# FPGA.net
KiCad netlist of a schematic drawn in EAGLE
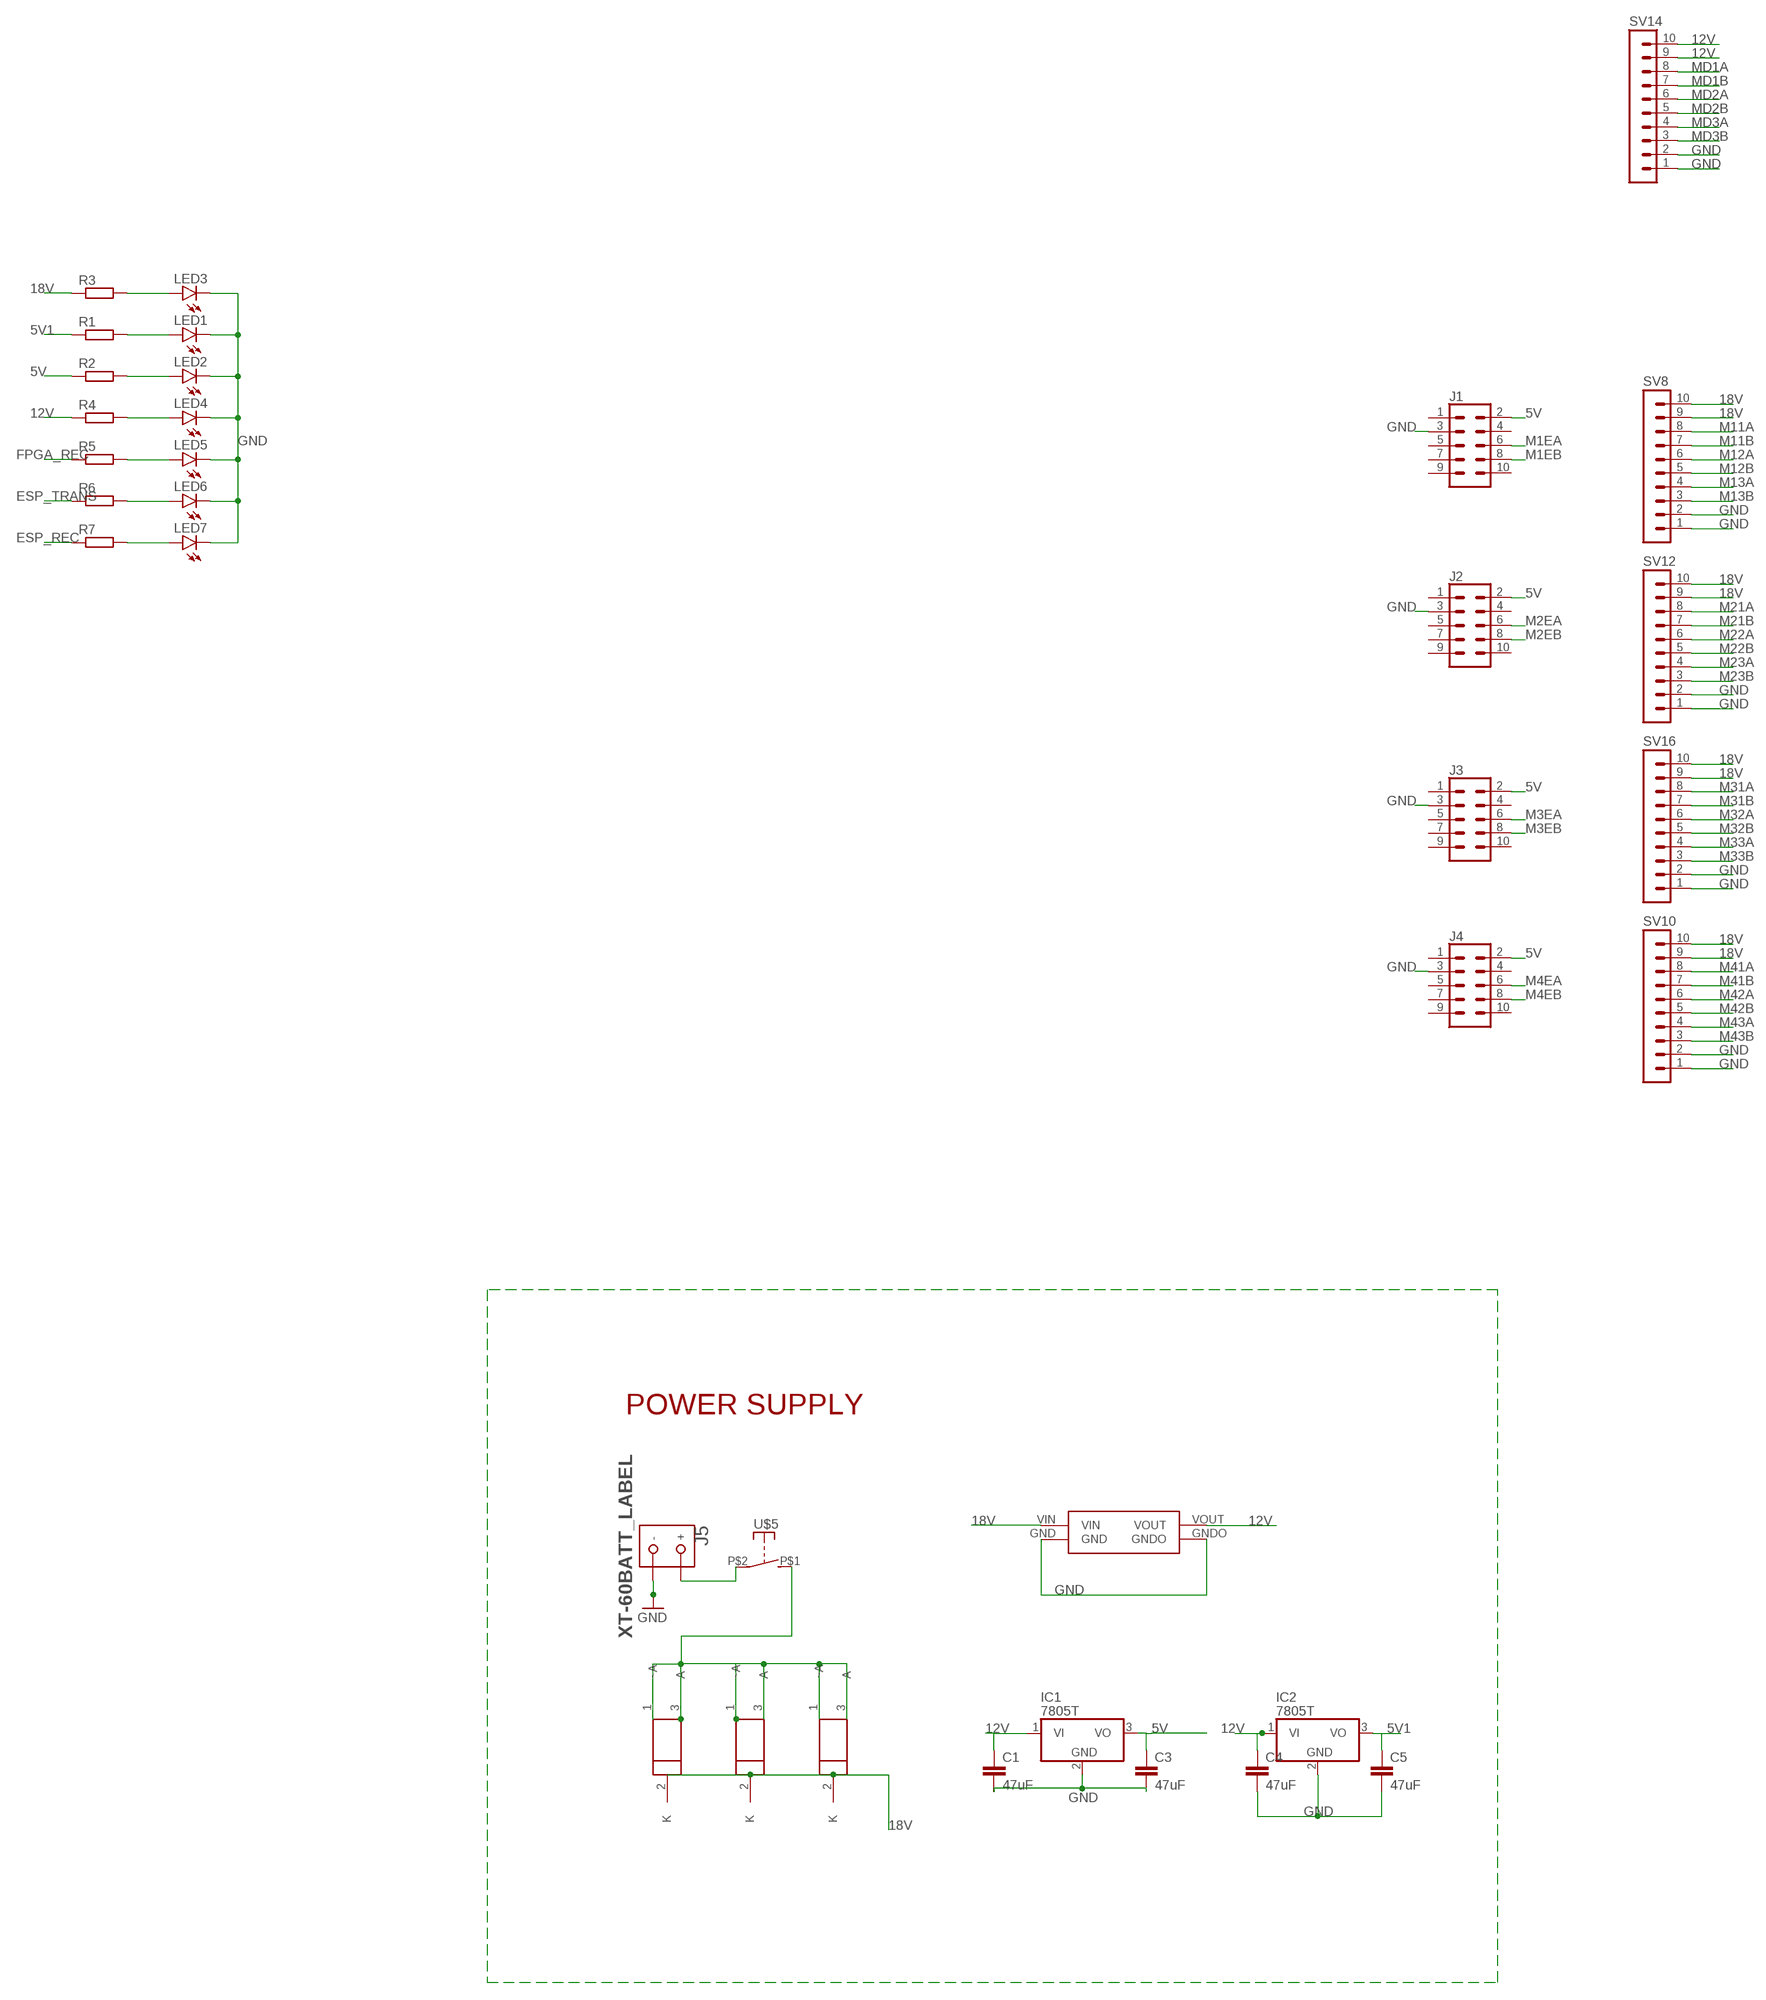
[diagram p0: schematic, sheet 1, part 1 of 2]
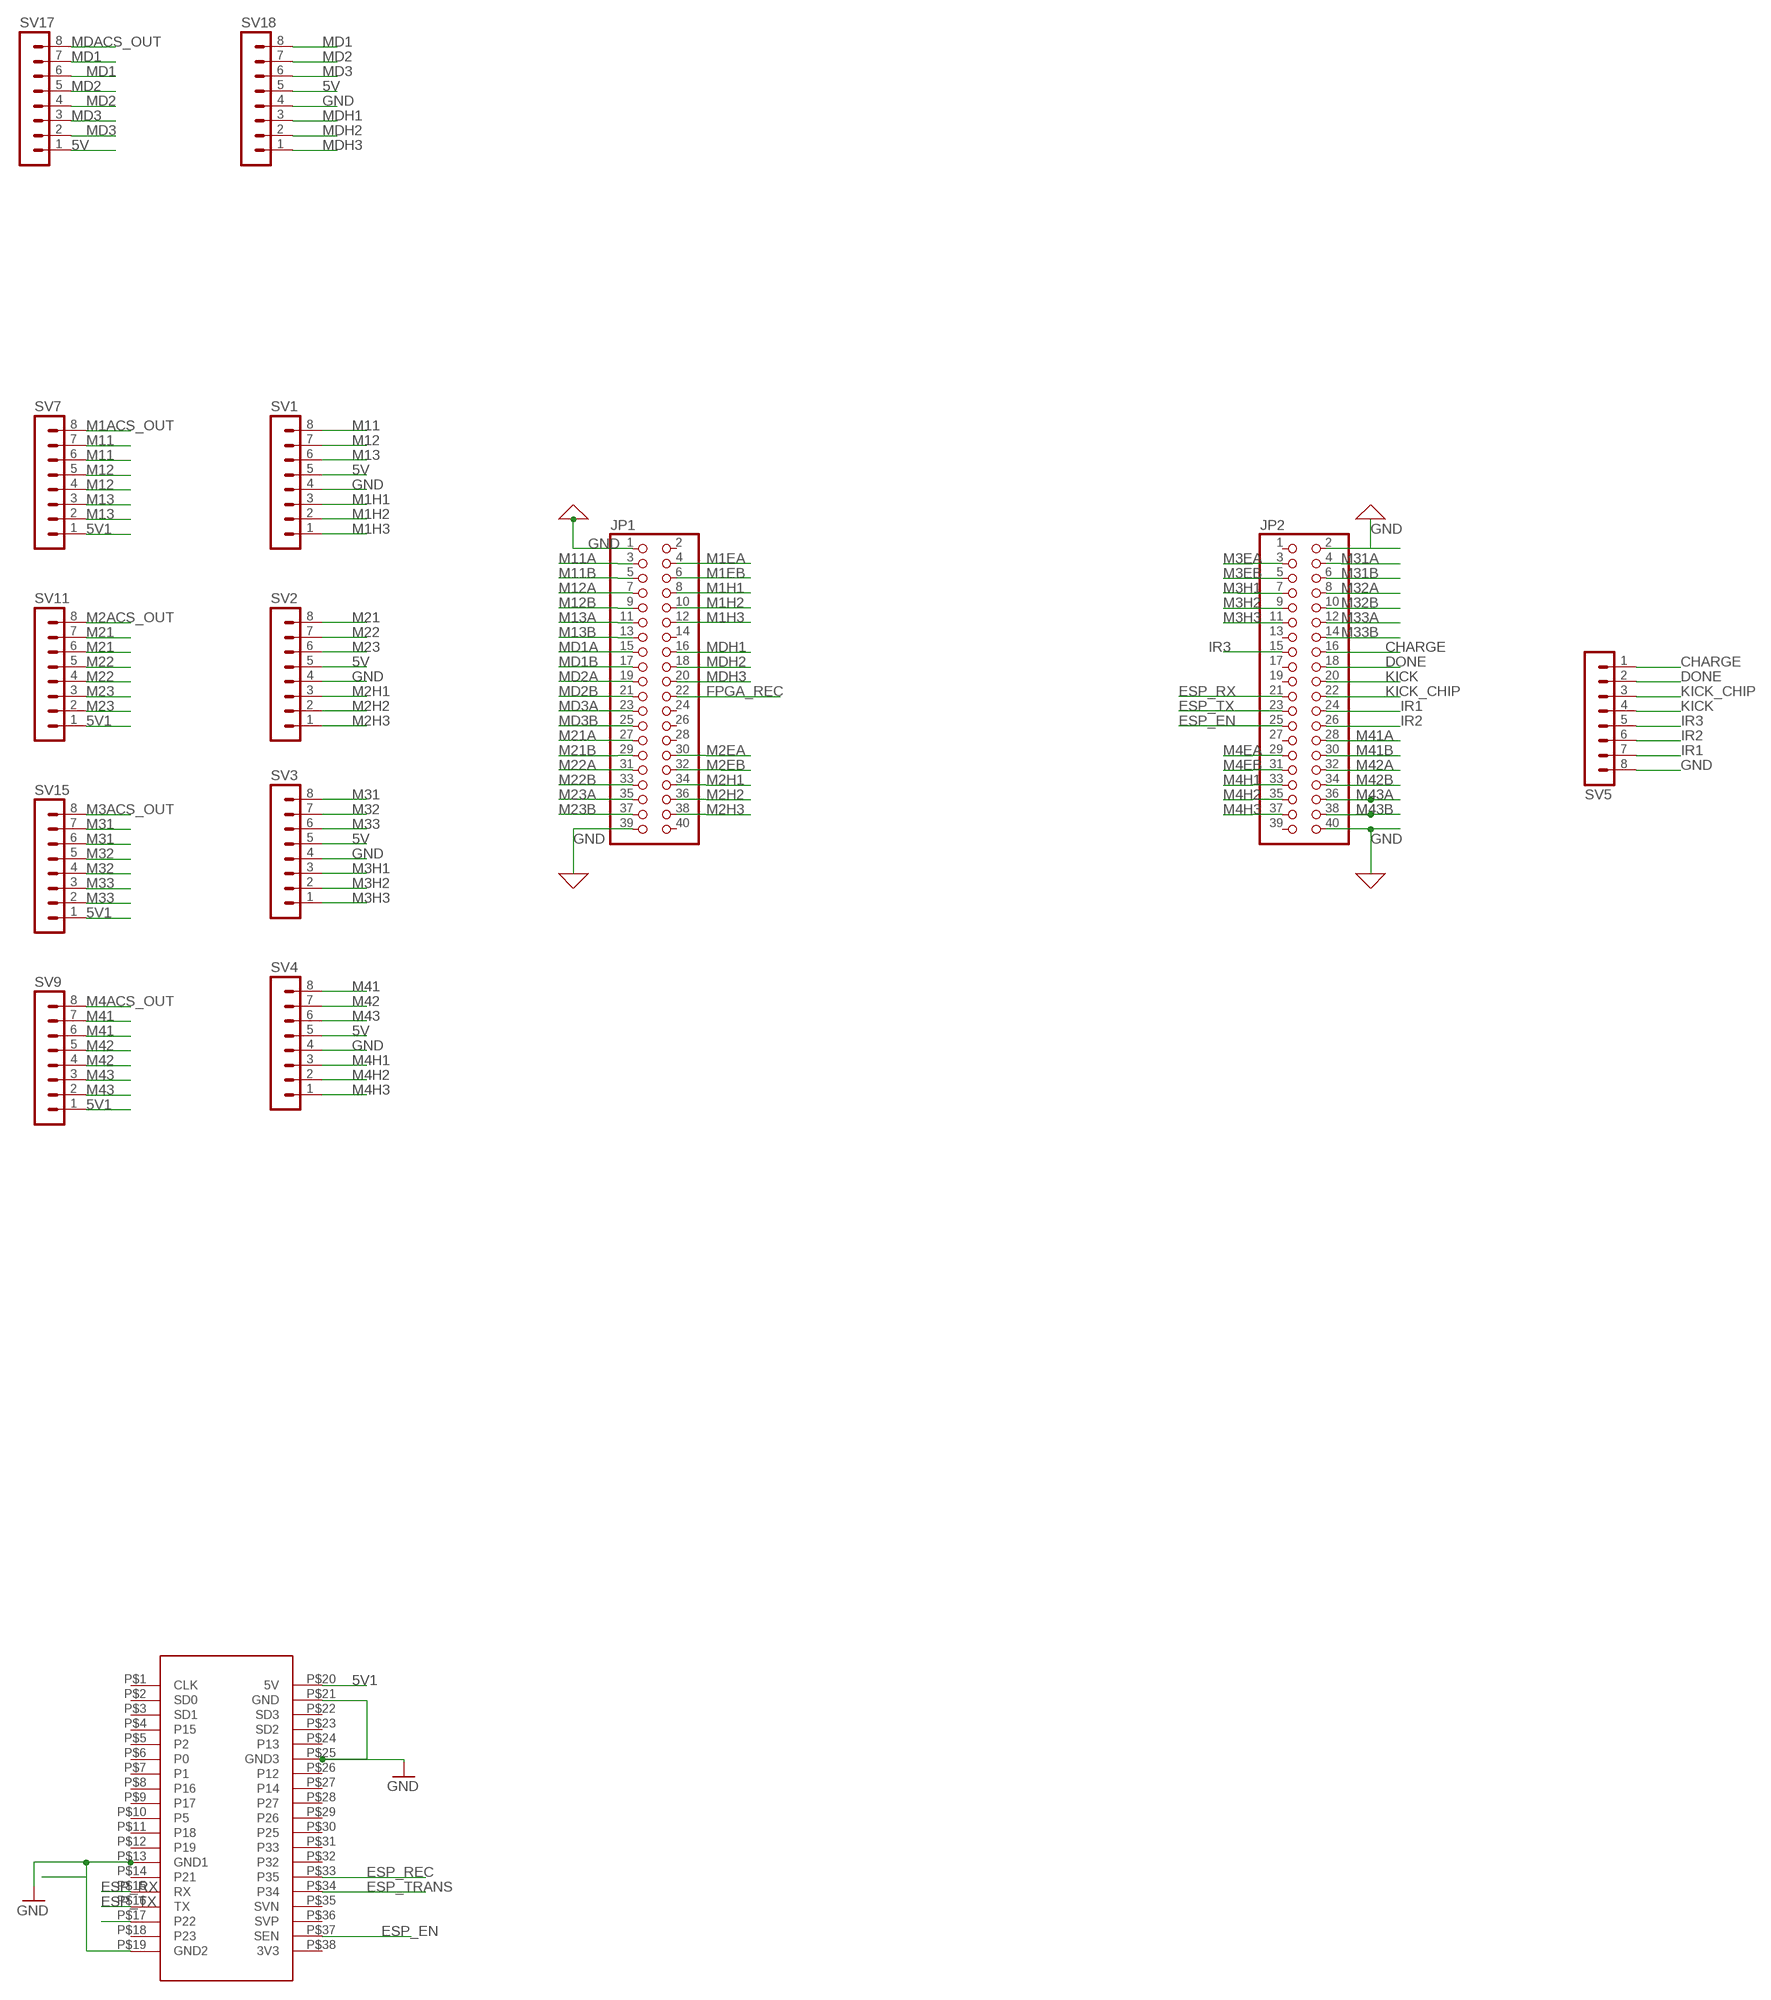
[diagram p1: schematic, sheet 1, part 2 of 2]

(export (version "E")
  (design (tool "Eeschema 10.0.6"))
  (components
    (comp (ref "C1")
      (value "47uF")
      (footprint "eagle-import:C1206")
      (libsource (lib "eagle-import") (part "C-EUC1206"))
    )
    (comp (ref "C3")
      (value "47uF")
      (footprint "eagle-import:C1206")
      (libsource (lib "eagle-import") (part "C-EUC1206"))
    )
    (comp (ref "C4")
      (value "47uF")
      (footprint "eagle-import:C1206")
      (libsource (lib "eagle-import") (part "C-EUC1206"))
    )
    (comp (ref "C5")
      (value "47uF")
      (footprint "eagle-import:C1206")
      (libsource (lib "eagle-import") (part "C-EUC1206"))
    )
    (comp (ref "IC1")
      (value "7805T")
      (footprint "eagle-import:TO220H")
      (libsource (lib "eagle-import") (part "78T05"))
    )
    (comp (ref "IC2")
      (value "7805T")
      (footprint "eagle-import:TO220H")
      (libsource (lib "eagle-import") (part "78T05"))
    )
    (comp (ref "J1")
      (value "CONN_05X2SHD_LOCK")
      (footprint "eagle-import:2X5-SHROUDED_LOCK")
      (libsource (lib "eagle-import") (part "CONN_05X2SHD_LOCK"))
    )
    (comp (ref "J2")
      (value "CONN_05X2SHD_LOCK")
      (footprint "eagle-import:2X5-SHROUDED_LOCK")
      (libsource (lib "eagle-import") (part "CONN_05X2SHD_LOCK"))
    )
    (comp (ref "J3")
      (value "CONN_05X2SHD_LOCK")
      (footprint "eagle-import:2X5-SHROUDED_LOCK")
      (libsource (lib "eagle-import") (part "CONN_05X2SHD_LOCK"))
    )
    (comp (ref "J4")
      (value "CONN_05X2SHD_LOCK")
      (footprint "eagle-import:2X5-SHROUDED_LOCK")
      (libsource (lib "eagle-import") (part "CONN_05X2SHD_LOCK"))
    )
    (comp (ref "J5")
      (value "XT-60BATT_LABEL")
      (footprint "eagle-import:XT-60")
      (libsource (lib "eagle-import") (part "XT-60BATT_LABEL"))
    )
    (comp (ref "JP1")
      (value "PINHD-2X20")
      (footprint "eagle-import:2X20")
      (libsource (lib "eagle-import") (part "PINHD-2X20"))
    )
    (comp (ref "JP2")
      (value "PINHD-2X20")
      (footprint "eagle-import:2X20")
      (libsource (lib "eagle-import") (part "PINHD-2X20"))
    )
    (comp (ref "LED1")
      (value "LEDSMT1206")
      (footprint "eagle-import:1206")
      (libsource (lib "eagle-import") (part "LEDSMT1206"))
    )
    (comp (ref "LED2")
      (value "LEDSMT1206")
      (footprint "eagle-import:1206")
      (libsource (lib "eagle-import") (part "LEDSMT1206"))
    )
    (comp (ref "LED3")
      (value "LEDSMT1206")
      (footprint "eagle-import:1206")
      (libsource (lib "eagle-import") (part "LEDSMT1206"))
    )
    (comp (ref "LED4")
      (value "LEDSMT1206")
      (footprint "eagle-import:1206")
      (libsource (lib "eagle-import") (part "LEDSMT1206"))
    )
    (comp (ref "LED5")
      (value "LEDSMT1206")
      (footprint "eagle-import:1206")
      (libsource (lib "eagle-import") (part "LEDSMT1206"))
    )
    (comp (ref "LED6")
      (value "LEDSMT1206")
      (footprint "eagle-import:1206")
      (libsource (lib "eagle-import") (part "LEDSMT1206"))
    )
    (comp (ref "LED7")
      (value "LEDSMT1206")
      (footprint "eagle-import:1206")
      (libsource (lib "eagle-import") (part "LEDSMT1206"))
    )
    (comp (ref "R1")
      (value "R-EU_R1206")
      (footprint "eagle-import:R1206")
      (libsource (lib "eagle-import") (part "R-EU_R1206"))
    )
    (comp (ref "R2")
      (value "R-EU_R1206")
      (footprint "eagle-import:R1206")
      (libsource (lib "eagle-import") (part "R-EU_R1206"))
    )
    (comp (ref "R3")
      (value "R-EU_R1206")
      (footprint "eagle-import:R1206")
      (libsource (lib "eagle-import") (part "R-EU_R1206"))
    )
    (comp (ref "R4")
      (value "R-EU_R1206")
      (footprint "eagle-import:R1206")
      (libsource (lib "eagle-import") (part "R-EU_R1206"))
    )
    (comp (ref "R5")
      (value "R-EU_R1206")
      (footprint "eagle-import:R1206")
      (libsource (lib "eagle-import") (part "R-EU_R1206"))
    )
    (comp (ref "R6")
      (value "R-EU_R1206")
      (footprint "eagle-import:R1206")
      (libsource (lib "eagle-import") (part "R-EU_R1206"))
    )
    (comp (ref "R7")
      (value "R-EU_R1206")
      (footprint "eagle-import:R1206")
      (libsource (lib "eagle-import") (part "R-EU_R1206"))
    )
    (comp (ref "SV1")
      (value "MA08-1")
      (footprint "eagle-import:MA08-1")
      (libsource (lib "eagle-import") (part "MA08-1"))
    )
    (comp (ref "SV2")
      (value "MA08-1")
      (footprint "eagle-import:MA08-1")
      (libsource (lib "eagle-import") (part "MA08-1"))
    )
    (comp (ref "SV3")
      (value "MA08-1")
      (footprint "eagle-import:MA08-1")
      (libsource (lib "eagle-import") (part "MA08-1"))
    )
    (comp (ref "SV4")
      (value "MA08-1")
      (footprint "eagle-import:MA08-1")
      (libsource (lib "eagle-import") (part "MA08-1"))
    )
    (comp (ref "SV5")
      (value "MA08-1")
      (footprint "eagle-import:MA08-1")
      (libsource (lib "eagle-import") (part "MA08-1"))
    )
    (comp (ref "SV7")
      (value "MA08-1")
      (footprint "eagle-import:MA08-1")
      (libsource (lib "eagle-import") (part "MA08-1"))
    )
    (comp (ref "SV8")
      (value "MA10-1")
      (footprint "eagle-import:MA10-1")
      (libsource (lib "eagle-import") (part "MA10-1"))
    )
    (comp (ref "SV9")
      (value "MA08-1")
      (footprint "eagle-import:MA08-1")
      (libsource (lib "eagle-import") (part "MA08-1"))
    )
    (comp (ref "SV10")
      (value "MA10-1")
      (footprint "eagle-import:MA10-1")
      (libsource (lib "eagle-import") (part "MA10-1"))
    )
    (comp (ref "SV11")
      (value "MA08-1")
      (footprint "eagle-import:MA08-1")
      (libsource (lib "eagle-import") (part "MA08-1"))
    )
    (comp (ref "SV12")
      (value "MA10-1")
      (footprint "eagle-import:MA10-1")
      (libsource (lib "eagle-import") (part "MA10-1"))
    )
    (comp (ref "SV14")
      (value "MA10-1")
      (footprint "eagle-import:MA10-1")
      (libsource (lib "eagle-import") (part "MA10-1"))
    )
    (comp (ref "SV15")
      (value "MA08-1")
      (footprint "eagle-import:MA08-1")
      (libsource (lib "eagle-import") (part "MA08-1"))
    )
    (comp (ref "SV16")
      (value "MA10-1")
      (footprint "eagle-import:MA10-1")
      (libsource (lib "eagle-import") (part "MA10-1"))
    )
    (comp (ref "SV17")
      (value "MA08-1")
      (footprint "eagle-import:MA08-1")
      (libsource (lib "eagle-import") (part "MA08-1"))
    )
    (comp (ref "SV18")
      (value "MA08-1")
      (footprint "eagle-import:MA08-1")
      (libsource (lib "eagle-import") (part "MA08-1"))
    )
    (comp (ref "U$1")
      (value "NODEMCU32S")
      (footprint "eagle-import:NODEMCU32")
      (libsource (lib "eagle-import") (part "NODEMCU32S"))
    )
    (comp (ref "U$4")
      (value "BUCK")
      (footprint "eagle-import:BUCK")
      (libsource (lib "eagle-import") (part "BUCK"))
    )
    (comp (ref "U$5")
      (value "SWITCH_DA10")
      (footprint "eagle-import:DA10")
      (libsource (lib "eagle-import") (part "SWITCH_DA10"))
    )
    (comp (ref "U1")
      (value "LP38690DT-3.3")
      (footprint "eagle-import:TO228P1042X238-3N")
      (libsource (lib "eagle-import") (part "LP38690DT-3.3"))
    )
    (comp (ref "U2")
      (value "LP38690DT-3.3")
      (footprint "eagle-import:TO228P1042X238-3N")
      (libsource (lib "eagle-import") (part "LP38690DT-3.3"))
    )
    (comp (ref "U3")
      (value "LP38690DT-3.3")
      (footprint "eagle-import:TO228P1042X238-3N")
      (libsource (lib "eagle-import") (part "LP38690DT-3.3"))
    )
  )
  (nets
    (net (code "1") (name "/5V") (class "Default")
      (node (ref "C3") (pin "1") (pinfunction "1_1") (pintype "passive"))
      (node (ref "IC1") (pin "3") (pinfunction "VO_3") (pintype "passive"))
      (node (ref "J1") (pin "2") (pinfunction "2_2") (pintype "passive"))
      (node (ref "J2") (pin "2") (pinfunction "2_2") (pintype "passive"))
      (node (ref "J3") (pin "2") (pinfunction "2_2") (pintype "passive"))
      (node (ref "J4") (pin "2") (pinfunction "2_2") (pintype "passive"))
      (node (ref "R2") (pin "1") (pinfunction "1_1") (pintype "passive"))
      (node (ref "SV1") (pin "5") (pinfunction "5_5") (pintype "passive"))
      (node (ref "SV17") (pin "1") (pinfunction "1_1") (pintype "passive"))
      (node (ref "SV18") (pin "5") (pinfunction "5_5") (pintype "passive"))
      (node (ref "SV2") (pin "5") (pinfunction "5_5") (pintype "passive"))
      (node (ref "SV3") (pin "5") (pinfunction "5_5") (pintype "passive"))
      (node (ref "SV4") (pin "5") (pinfunction "5_5") (pintype "passive"))
    )
    (net (code "2") (name "/5V1") (class "Default")
      (node (ref "C5") (pin "1") (pinfunction "1_1") (pintype "passive"))
      (node (ref "IC2") (pin "3") (pinfunction "VO_3") (pintype "passive"))
      (node (ref "R1") (pin "1") (pinfunction "1_1") (pintype "passive"))
      (node (ref "SV11") (pin "1") (pinfunction "1_1") (pintype "passive"))
      (node (ref "SV15") (pin "1") (pinfunction "1_1") (pintype "passive"))
      (node (ref "SV7") (pin "1") (pinfunction "1_1") (pintype "passive"))
      (node (ref "SV9") (pin "1") (pinfunction "1_1") (pintype "passive"))
      (node (ref "U$1") (pin "P$20") (pinfunction "5V_P$20") (pintype "bidirectional"))
    )
    (net (code "3") (name "/12V") (class "Default")
      (node (ref "C1") (pin "1") (pinfunction "1_1") (pintype "passive"))
      (node (ref "C4") (pin "1") (pinfunction "1_1") (pintype "passive"))
      (node (ref "IC1") (pin "1") (pinfunction "VI_1") (pintype "input"))
      (node (ref "IC2") (pin "1") (pinfunction "VI_1") (pintype "input"))
      (node (ref "R4") (pin "1") (pinfunction "1_1") (pintype "passive"))
      (node (ref "SV14") (pin "10") (pinfunction "10_10") (pintype "passive"))
      (node (ref "SV14") (pin "9") (pinfunction "9_9") (pintype "passive"))
      (node (ref "U$4") (pin "VOUT") (pinfunction "VOUT_VOUT") (pintype "bidirectional"))
    )
    (net (code "4") (name "/18V") (class "Default")
      (node (ref "R3") (pin "1") (pinfunction "1_1") (pintype "passive"))
      (node (ref "SV10") (pin "10") (pinfunction "10_10") (pintype "passive"))
      (node (ref "SV10") (pin "9") (pinfunction "9_9") (pintype "passive"))
      (node (ref "SV12") (pin "10") (pinfunction "10_10") (pintype "passive"))
      (node (ref "SV12") (pin "9") (pinfunction "9_9") (pintype "passive"))
      (node (ref "SV16") (pin "10") (pinfunction "10_10") (pintype "passive"))
      (node (ref "SV16") (pin "9") (pinfunction "9_9") (pintype "passive"))
      (node (ref "SV8") (pin "10") (pinfunction "10_10") (pintype "passive"))
      (node (ref "SV8") (pin "9") (pinfunction "9_9") (pintype "passive"))
      (node (ref "U$4") (pin "VIN") (pinfunction "VIN_VIN") (pintype "bidirectional"))
      (node (ref "U1") (pin "2") (pinfunction "K_2") (pintype "bidirectional"))
      (node (ref "U2") (pin "2") (pinfunction "K_2") (pintype "bidirectional"))
      (node (ref "U3") (pin "2") (pinfunction "K_2") (pintype "bidirectional"))
    )
    (net (code "5") (name "/CHARGE") (class "Default")
      (node (ref "JP2") (pin "16") (pinfunction "16_16") (pintype "passive"))
      (node (ref "SV5") (pin "1") (pinfunction "1_1") (pintype "passive"))
    )
    (net (code "6") (name "/DONE") (class "Default")
      (node (ref "JP2") (pin "18") (pinfunction "18_18") (pintype "passive"))
      (node (ref "SV5") (pin "2") (pinfunction "2_2") (pintype "passive"))
    )
    (net (code "7") (name "/ESP_EN") (class "Default")
      (node (ref "JP2") (pin "25") (pinfunction "25_25") (pintype "passive"))
      (node (ref "U$1") (pin "P$37") (pinfunction "SEN_P$37") (pintype "bidirectional"))
    )
    (net (code "8") (name "/ESP_REC") (class "Default")
      (node (ref "R7") (pin "1") (pinfunction "1_1") (pintype "passive"))
      (node (ref "U$1") (pin "P$33") (pinfunction "P35_P$33") (pintype "bidirectional"))
    )
    (net (code "9") (name "/ESP_RX") (class "Default")
      (node (ref "JP2") (pin "21") (pinfunction "21_21") (pintype "passive"))
      (node (ref "U$1") (pin "P$15") (pinfunction "RX_P$15") (pintype "bidirectional"))
    )
    (net (code "10") (name "/ESP_TRANS") (class "Default")
      (node (ref "R6") (pin "1") (pinfunction "1_1") (pintype "passive"))
      (node (ref "U$1") (pin "P$34") (pinfunction "P34_P$34") (pintype "bidirectional"))
    )
    (net (code "11") (name "/ESP_TX") (class "Default")
      (node (ref "JP2") (pin "23") (pinfunction "23_23") (pintype "passive"))
      (node (ref "U$1") (pin "P$16") (pinfunction "TX_P$16") (pintype "bidirectional"))
    )
    (net (code "12") (name "/FPGA_REC") (class "Default")
      (node (ref "JP1") (pin "22") (pinfunction "22_22") (pintype "passive"))
      (node (ref "R5") (pin "1") (pinfunction "1_1") (pintype "passive"))
    )
    (net (code "13") (name "/IR1") (class "Default")
      (node (ref "JP2") (pin "24") (pinfunction "24_24") (pintype "passive"))
      (node (ref "SV5") (pin "7") (pinfunction "7_7") (pintype "passive"))
    )
    (net (code "14") (name "/IR2") (class "Default")
      (node (ref "JP2") (pin "26") (pinfunction "26_26") (pintype "passive"))
      (node (ref "SV5") (pin "6") (pinfunction "6_6") (pintype "passive"))
    )
    (net (code "15") (name "/IR3") (class "Default")
      (node (ref "JP2") (pin "15") (pinfunction "15_15") (pintype "passive"))
      (node (ref "SV5") (pin "5") (pinfunction "5_5") (pintype "passive"))
    )
    (net (code "16") (name "/KICK") (class "Default")
      (node (ref "JP2") (pin "20") (pinfunction "20_20") (pintype "passive"))
      (node (ref "SV5") (pin "4") (pinfunction "4_4") (pintype "passive"))
    )
    (net (code "17") (name "/KICK_CHIP") (class "Default")
      (node (ref "JP2") (pin "22") (pinfunction "22_22") (pintype "passive"))
      (node (ref "SV5") (pin "3") (pinfunction "3_3") (pintype "passive"))
    )
    (net (code "18") (name "/M1ACS_OUT") (class "Default")
      (node (ref "SV7") (pin "8") (pinfunction "8_8") (pintype "passive"))
    )
    (net (code "19") (name "/M1EA") (class "Default")
      (node (ref "J1") (pin "6") (pinfunction "6_6") (pintype "passive"))
      (node (ref "JP1") (pin "4") (pinfunction "4_4") (pintype "passive"))
    )
    (net (code "20") (name "/M1EB") (class "Default")
      (node (ref "J1") (pin "8") (pinfunction "8_8") (pintype "passive"))
      (node (ref "JP1") (pin "6") (pinfunction "6_6") (pintype "passive"))
    )
    (net (code "21") (name "/M1H1") (class "Default")
      (node (ref "JP1") (pin "8") (pinfunction "8_8") (pintype "passive"))
      (node (ref "SV1") (pin "3") (pinfunction "3_3") (pintype "passive"))
    )
    (net (code "22") (name "/M1H2") (class "Default")
      (node (ref "JP1") (pin "10") (pinfunction "10_10") (pintype "passive"))
      (node (ref "SV1") (pin "2") (pinfunction "2_2") (pintype "passive"))
    )
    (net (code "23") (name "/M1H3") (class "Default")
      (node (ref "JP1") (pin "12") (pinfunction "12_12") (pintype "passive"))
      (node (ref "SV1") (pin "1") (pinfunction "1_1") (pintype "passive"))
    )
    (net (code "24") (name "/M2ACS_OUT") (class "Default")
      (node (ref "SV11") (pin "8") (pinfunction "8_8") (pintype "passive"))
    )
    (net (code "25") (name "/M2EA") (class "Default")
      (node (ref "J2") (pin "6") (pinfunction "6_6") (pintype "passive"))
      (node (ref "JP1") (pin "30") (pinfunction "30_30") (pintype "passive"))
    )
    (net (code "26") (name "/M2EB") (class "Default")
      (node (ref "J2") (pin "8") (pinfunction "8_8") (pintype "passive"))
      (node (ref "JP1") (pin "32") (pinfunction "32_32") (pintype "passive"))
    )
    (net (code "27") (name "/M2H1") (class "Default")
      (node (ref "JP1") (pin "34") (pinfunction "34_34") (pintype "passive"))
      (node (ref "SV2") (pin "3") (pinfunction "3_3") (pintype "passive"))
    )
    (net (code "28") (name "/M2H2") (class "Default")
      (node (ref "JP1") (pin "36") (pinfunction "36_36") (pintype "passive"))
      (node (ref "SV2") (pin "2") (pinfunction "2_2") (pintype "passive"))
    )
    (net (code "29") (name "/M2H3") (class "Default")
      (node (ref "JP1") (pin "38") (pinfunction "38_38") (pintype "passive"))
      (node (ref "SV2") (pin "1") (pinfunction "1_1") (pintype "passive"))
    )
    (net (code "30") (name "/M3ACS_OUT") (class "Default")
      (node (ref "SV15") (pin "8") (pinfunction "8_8") (pintype "passive"))
    )
    (net (code "31") (name "/M3EA") (class "Default")
      (node (ref "J3") (pin "6") (pinfunction "6_6") (pintype "passive"))
      (node (ref "JP2") (pin "3") (pinfunction "3_3") (pintype "passive"))
    )
    (net (code "32") (name "/M3EB") (class "Default")
      (node (ref "J3") (pin "8") (pinfunction "8_8") (pintype "passive"))
      (node (ref "JP2") (pin "5") (pinfunction "5_5") (pintype "passive"))
    )
    (net (code "33") (name "/M3H1") (class "Default")
      (node (ref "JP2") (pin "7") (pinfunction "7_7") (pintype "passive"))
      (node (ref "SV3") (pin "3") (pinfunction "3_3") (pintype "passive"))
    )
    (net (code "34") (name "/M3H2") (class "Default")
      (node (ref "JP2") (pin "9") (pinfunction "9_9") (pintype "passive"))
      (node (ref "SV3") (pin "2") (pinfunction "2_2") (pintype "passive"))
    )
    (net (code "35") (name "/M3H3") (class "Default")
      (node (ref "JP2") (pin "11") (pinfunction "11_11") (pintype "passive"))
      (node (ref "SV3") (pin "1") (pinfunction "1_1") (pintype "passive"))
    )
    (net (code "36") (name "/M4ACS_OUT") (class "Default")
      (node (ref "SV9") (pin "8") (pinfunction "8_8") (pintype "passive"))
    )
    (net (code "37") (name "/M4EA") (class "Default")
      (node (ref "J4") (pin "6") (pinfunction "6_6") (pintype "passive"))
      (node (ref "JP2") (pin "29") (pinfunction "29_29") (pintype "passive"))
    )
    (net (code "38") (name "/M4EB") (class "Default")
      (node (ref "J4") (pin "8") (pinfunction "8_8") (pintype "passive"))
      (node (ref "JP2") (pin "31") (pinfunction "31_31") (pintype "passive"))
    )
    (net (code "39") (name "/M4H1") (class "Default")
      (node (ref "JP2") (pin "33") (pinfunction "33_33") (pintype "passive"))
      (node (ref "SV4") (pin "3") (pinfunction "3_3") (pintype "passive"))
    )
    (net (code "40") (name "/M4H2") (class "Default")
      (node (ref "JP2") (pin "35") (pinfunction "35_35") (pintype "passive"))
      (node (ref "SV4") (pin "2") (pinfunction "2_2") (pintype "passive"))
    )
    (net (code "41") (name "/M4H3") (class "Default")
      (node (ref "JP2") (pin "37") (pinfunction "37_37") (pintype "passive"))
      (node (ref "SV4") (pin "1") (pinfunction "1_1") (pintype "passive"))
    )
    (net (code "42") (name "/M11") (class "Default")
      (node (ref "SV1") (pin "8") (pinfunction "8_8") (pintype "passive"))
      (node (ref "SV7") (pin "6") (pinfunction "6_6") (pintype "passive"))
      (node (ref "SV7") (pin "7") (pinfunction "7_7") (pintype "passive"))
    )
    (net (code "43") (name "/M11A") (class "Default")
      (node (ref "JP1") (pin "3") (pinfunction "3_3") (pintype "passive"))
      (node (ref "SV8") (pin "8") (pinfunction "8_8") (pintype "passive"))
    )
    (net (code "44") (name "/M11B") (class "Default")
      (node (ref "JP1") (pin "5") (pinfunction "5_5") (pintype "passive"))
      (node (ref "SV8") (pin "7") (pinfunction "7_7") (pintype "passive"))
    )
    (net (code "45") (name "/M12") (class "Default")
      (node (ref "SV1") (pin "7") (pinfunction "7_7") (pintype "passive"))
      (node (ref "SV7") (pin "4") (pinfunction "4_4") (pintype "passive"))
      (node (ref "SV7") (pin "5") (pinfunction "5_5") (pintype "passive"))
    )
    (net (code "46") (name "/M12A") (class "Default")
      (node (ref "JP1") (pin "7") (pinfunction "7_7") (pintype "passive"))
      (node (ref "SV8") (pin "6") (pinfunction "6_6") (pintype "passive"))
    )
    (net (code "47") (name "/M12B") (class "Default")
      (node (ref "JP1") (pin "9") (pinfunction "9_9") (pintype "passive"))
      (node (ref "SV8") (pin "5") (pinfunction "5_5") (pintype "passive"))
    )
    (net (code "48") (name "/M13") (class "Default")
      (node (ref "SV1") (pin "6") (pinfunction "6_6") (pintype "passive"))
      (node (ref "SV7") (pin "2") (pinfunction "2_2") (pintype "passive"))
      (node (ref "SV7") (pin "3") (pinfunction "3_3") (pintype "passive"))
    )
    (net (code "49") (name "/M13A") (class "Default")
      (node (ref "JP1") (pin "11") (pinfunction "11_11") (pintype "passive"))
      (node (ref "SV8") (pin "4") (pinfunction "4_4") (pintype "passive"))
    )
    (net (code "50") (name "/M13B") (class "Default")
      (node (ref "JP1") (pin "13") (pinfunction "13_13") (pintype "passive"))
      (node (ref "SV8") (pin "3") (pinfunction "3_3") (pintype "passive"))
    )
    (net (code "51") (name "/M21") (class "Default")
      (node (ref "SV11") (pin "6") (pinfunction "6_6") (pintype "passive"))
      (node (ref "SV11") (pin "7") (pinfunction "7_7") (pintype "passive"))
      (node (ref "SV2") (pin "8") (pinfunction "8_8") (pintype "passive"))
    )
    (net (code "52") (name "/M21A") (class "Default")
      (node (ref "JP1") (pin "27") (pinfunction "27_27") (pintype "passive"))
      (node (ref "SV12") (pin "8") (pinfunction "8_8") (pintype "passive"))
    )
    (net (code "53") (name "/M21B") (class "Default")
      (node (ref "JP1") (pin "29") (pinfunction "29_29") (pintype "passive"))
      (node (ref "SV12") (pin "7") (pinfunction "7_7") (pintype "passive"))
    )
    (net (code "54") (name "/M22") (class "Default")
      (node (ref "SV11") (pin "4") (pinfunction "4_4") (pintype "passive"))
      (node (ref "SV11") (pin "5") (pinfunction "5_5") (pintype "passive"))
      (node (ref "SV2") (pin "7") (pinfunction "7_7") (pintype "passive"))
    )
    (net (code "55") (name "/M22A") (class "Default")
      (node (ref "JP1") (pin "31") (pinfunction "31_31") (pintype "passive"))
      (node (ref "SV12") (pin "6") (pinfunction "6_6") (pintype "passive"))
    )
    (net (code "56") (name "/M22B") (class "Default")
      (node (ref "JP1") (pin "33") (pinfunction "33_33") (pintype "passive"))
      (node (ref "SV12") (pin "5") (pinfunction "5_5") (pintype "passive"))
    )
    (net (code "57") (name "/M23") (class "Default")
      (node (ref "SV11") (pin "2") (pinfunction "2_2") (pintype "passive"))
      (node (ref "SV11") (pin "3") (pinfunction "3_3") (pintype "passive"))
      (node (ref "SV2") (pin "6") (pinfunction "6_6") (pintype "passive"))
    )
    (net (code "58") (name "/M23A") (class "Default")
      (node (ref "JP1") (pin "35") (pinfunction "35_35") (pintype "passive"))
      (node (ref "SV12") (pin "4") (pinfunction "4_4") (pintype "passive"))
    )
    (net (code "59") (name "/M23B") (class "Default")
      (node (ref "JP1") (pin "37") (pinfunction "37_37") (pintype "passive"))
      (node (ref "SV12") (pin "3") (pinfunction "3_3") (pintype "passive"))
    )
    (net (code "60") (name "/M31") (class "Default")
      (node (ref "SV15") (pin "6") (pinfunction "6_6") (pintype "passive"))
      (node (ref "SV15") (pin "7") (pinfunction "7_7") (pintype "passive"))
      (node (ref "SV3") (pin "8") (pinfunction "8_8") (pintype "passive"))
    )
    (net (code "61") (name "/M31A") (class "Default")
      (node (ref "JP2") (pin "4") (pinfunction "4_4") (pintype "passive"))
      (node (ref "SV16") (pin "8") (pinfunction "8_8") (pintype "passive"))
    )
    (net (code "62") (name "/M31B") (class "Default")
      (node (ref "JP2") (pin "6") (pinfunction "6_6") (pintype "passive"))
      (node (ref "SV16") (pin "7") (pinfunction "7_7") (pintype "passive"))
    )
    (net (code "63") (name "/M32") (class "Default")
      (node (ref "SV15") (pin "4") (pinfunction "4_4") (pintype "passive"))
      (node (ref "SV15") (pin "5") (pinfunction "5_5") (pintype "passive"))
      (node (ref "SV3") (pin "7") (pinfunction "7_7") (pintype "passive"))
    )
    (net (code "64") (name "/M32A") (class "Default")
      (node (ref "JP2") (pin "8") (pinfunction "8_8") (pintype "passive"))
      (node (ref "SV16") (pin "6") (pinfunction "6_6") (pintype "passive"))
    )
    (net (code "65") (name "/M32B") (class "Default")
      (node (ref "JP2") (pin "10") (pinfunction "10_10") (pintype "passive"))
      (node (ref "SV16") (pin "5") (pinfunction "5_5") (pintype "passive"))
    )
    (net (code "66") (name "/M33") (class "Default")
      (node (ref "SV15") (pin "2") (pinfunction "2_2") (pintype "passive"))
      (node (ref "SV15") (pin "3") (pinfunction "3_3") (pintype "passive"))
      (node (ref "SV3") (pin "6") (pinfunction "6_6") (pintype "passive"))
    )
    (net (code "67") (name "/M33A") (class "Default")
      (node (ref "JP2") (pin "12") (pinfunction "12_12") (pintype "passive"))
      (node (ref "SV16") (pin "4") (pinfunction "4_4") (pintype "passive"))
    )
    (net (code "68") (name "/M33B") (class "Default")
      (node (ref "JP2") (pin "14") (pinfunction "14_14") (pintype "passive"))
      (node (ref "SV16") (pin "3") (pinfunction "3_3") (pintype "passive"))
    )
    (net (code "69") (name "/M41") (class "Default")
      (node (ref "SV4") (pin "8") (pinfunction "8_8") (pintype "passive"))
      (node (ref "SV9") (pin "6") (pinfunction "6_6") (pintype "passive"))
      (node (ref "SV9") (pin "7") (pinfunction "7_7") (pintype "passive"))
    )
    (net (code "70") (name "/M41A") (class "Default")
      (node (ref "JP2") (pin "28") (pinfunction "28_28") (pintype "passive"))
      (node (ref "SV10") (pin "8") (pinfunction "8_8") (pintype "passive"))
    )
    (net (code "71") (name "/M41B") (class "Default")
      (node (ref "JP2") (pin "30") (pinfunction "30_30") (pintype "passive"))
      (node (ref "SV10") (pin "7") (pinfunction "7_7") (pintype "passive"))
    )
    (net (code "72") (name "/M42") (class "Default")
      (node (ref "SV4") (pin "7") (pinfunction "7_7") (pintype "passive"))
      (node (ref "SV9") (pin "4") (pinfunction "4_4") (pintype "passive"))
      (node (ref "SV9") (pin "5") (pinfunction "5_5") (pintype "passive"))
    )
    (net (code "73") (name "/M42A") (class "Default")
      (node (ref "JP2") (pin "32") (pinfunction "32_32") (pintype "passive"))
      (node (ref "SV10") (pin "6") (pinfunction "6_6") (pintype "passive"))
    )
    (net (code "74") (name "/M42B") (class "Default")
      (node (ref "JP2") (pin "34") (pinfunction "34_34") (pintype "passive"))
      (node (ref "SV10") (pin "5") (pinfunction "5_5") (pintype "passive"))
    )
    (net (code "75") (name "/M43") (class "Default")
      (node (ref "SV4") (pin "6") (pinfunction "6_6") (pintype "passive"))
      (node (ref "SV9") (pin "2") (pinfunction "2_2") (pintype "passive"))
      (node (ref "SV9") (pin "3") (pinfunction "3_3") (pintype "passive"))
    )
    (net (code "76") (name "/M43A") (class "Default")
      (node (ref "JP2") (pin "36") (pinfunction "36_36") (pintype "passive"))
      (node (ref "SV10") (pin "4") (pinfunction "4_4") (pintype "passive"))
    )
    (net (code "77") (name "/M43B") (class "Default")
      (node (ref "JP2") (pin "38") (pinfunction "38_38") (pintype "passive"))
      (node (ref "SV10") (pin "3") (pinfunction "3_3") (pintype "passive"))
    )
    (net (code "78") (name "/MD1") (class "Default")
      (node (ref "SV17") (pin "6") (pinfunction "6_6") (pintype "passive"))
      (node (ref "SV17") (pin "7") (pinfunction "7_7") (pintype "passive"))
      (node (ref "SV18") (pin "8") (pinfunction "8_8") (pintype "passive"))
    )
    (net (code "79") (name "/MD1A") (class "Default")
      (node (ref "JP1") (pin "15") (pinfunction "15_15") (pintype "passive"))
      (node (ref "SV14") (pin "8") (pinfunction "8_8") (pintype "passive"))
    )
    (net (code "80") (name "/MD1B") (class "Default")
      (node (ref "JP1") (pin "17") (pinfunction "17_17") (pintype "passive"))
      (node (ref "SV14") (pin "7") (pinfunction "7_7") (pintype "passive"))
    )
    (net (code "81") (name "/MD2") (class "Default")
      (node (ref "SV17") (pin "4") (pinfunction "4_4") (pintype "passive"))
      (node (ref "SV17") (pin "5") (pinfunction "5_5") (pintype "passive"))
      (node (ref "SV18") (pin "7") (pinfunction "7_7") (pintype "passive"))
    )
    (net (code "82") (name "/MD2A") (class "Default")
      (node (ref "JP1") (pin "19") (pinfunction "19_19") (pintype "passive"))
      (node (ref "SV14") (pin "6") (pinfunction "6_6") (pintype "passive"))
    )
    (net (code "83") (name "/MD2B") (class "Default")
      (node (ref "JP1") (pin "21") (pinfunction "21_21") (pintype "passive"))
      (node (ref "SV14") (pin "5") (pinfunction "5_5") (pintype "passive"))
    )
    (net (code "84") (name "/MD3") (class "Default")
      (node (ref "SV17") (pin "2") (pinfunction "2_2") (pintype "passive"))
      (node (ref "SV17") (pin "3") (pinfunction "3_3") (pintype "passive"))
      (node (ref "SV18") (pin "6") (pinfunction "6_6") (pintype "passive"))
    )
    (net (code "85") (name "/MD3A") (class "Default")
      (node (ref "JP1") (pin "23") (pinfunction "23_23") (pintype "passive"))
      (node (ref "SV14") (pin "4") (pinfunction "4_4") (pintype "passive"))
    )
    (net (code "86") (name "/MD3B") (class "Default")
      (node (ref "JP1") (pin "25") (pinfunction "25_25") (pintype "passive"))
      (node (ref "SV14") (pin "3") (pinfunction "3_3") (pintype "passive"))
    )
    (net (code "87") (name "/MDACS_OUT") (class "Default")
      (node (ref "SV17") (pin "8") (pinfunction "8_8") (pintype "passive"))
    )
    (net (code "88") (name "/MDH1") (class "Default")
      (node (ref "JP1") (pin "16") (pinfunction "16_16") (pintype "passive"))
      (node (ref "SV18") (pin "3") (pinfunction "3_3") (pintype "passive"))
    )
    (net (code "89") (name "/MDH2") (class "Default")
      (node (ref "JP1") (pin "18") (pinfunction "18_18") (pintype "passive"))
      (node (ref "SV18") (pin "2") (pinfunction "2_2") (pintype "passive"))
    )
    (net (code "90") (name "/MDH3") (class "Default")
      (node (ref "JP1") (pin "20") (pinfunction "20_20") (pintype "passive"))
      (node (ref "SV18") (pin "1") (pinfunction "1_1") (pintype "passive"))
    )
    (net (code "91") (name "GND") (class "Default")
      (node (ref "C1") (pin "2") (pinfunction "2_2") (pintype "passive"))
      (node (ref "C3") (pin "2") (pinfunction "2_2") (pintype "passive"))
      (node (ref "C4") (pin "2") (pinfunction "2_2") (pintype "passive"))
      (node (ref "C5") (pin "2") (pinfunction "2_2") (pintype "passive"))
      (node (ref "IC1") (pin "2") (pinfunction "GND_2") (pintype "passive"))
      (node (ref "IC2") (pin "2") (pinfunction "GND_2") (pintype "passive"))
      (node (ref "J1") (pin "3") (pinfunction "3_3") (pintype "passive"))
      (node (ref "J2") (pin "3") (pinfunction "3_3") (pintype "passive"))
      (node (ref "J3") (pin "3") (pinfunction "3_3") (pintype "passive"))
      (node (ref "J4") (pin "3") (pinfunction "3_3") (pintype "passive"))
      (node (ref "J5") (pin "GND") (pinfunction "-_GND") (pintype "passive"))
      (node (ref "JP1") (pin "1") (pinfunction "1_1") (pintype "passive"))
      (node (ref "JP1") (pin "39") (pinfunction "39_39") (pintype "passive"))
      (node (ref "JP2") (pin "2") (pinfunction "2_2") (pintype "passive"))
      (node (ref "JP2") (pin "40") (pinfunction "40_40") (pintype "passive"))
      (node (ref "LED1") (pin "C") (pinfunction "C_C") (pintype "passive"))
      (node (ref "LED2") (pin "C") (pinfunction "C_C") (pintype "passive"))
      (node (ref "LED3") (pin "C") (pinfunction "C_C") (pintype "passive"))
      (node (ref "LED4") (pin "C") (pinfunction "C_C") (pintype "passive"))
      (node (ref "LED5") (pin "C") (pinfunction "C_C") (pintype "passive"))
      (node (ref "LED6") (pin "C") (pinfunction "C_C") (pintype "passive"))
      (node (ref "LED7") (pin "C") (pinfunction "C_C") (pintype "passive"))
      (node (ref "SV1") (pin "4") (pinfunction "4_4") (pintype "passive"))
      (node (ref "SV10") (pin "1") (pinfunction "1_1") (pintype "passive"))
      (node (ref "SV10") (pin "2") (pinfunction "2_2") (pintype "passive"))
      (node (ref "SV12") (pin "1") (pinfunction "1_1") (pintype "passive"))
      (node (ref "SV12") (pin "2") (pinfunction "2_2") (pintype "passive"))
      (node (ref "SV14") (pin "1") (pinfunction "1_1") (pintype "passive"))
      (node (ref "SV14") (pin "2") (pinfunction "2_2") (pintype "passive"))
      (node (ref "SV16") (pin "1") (pinfunction "1_1") (pintype "passive"))
      (node (ref "SV16") (pin "2") (pinfunction "2_2") (pintype "passive"))
      (node (ref "SV18") (pin "4") (pinfunction "4_4") (pintype "passive"))
      (node (ref "SV2") (pin "4") (pinfunction "4_4") (pintype "passive"))
      (node (ref "SV3") (pin "4") (pinfunction "4_4") (pintype "passive"))
      (node (ref "SV4") (pin "4") (pinfunction "4_4") (pintype "passive"))
      (node (ref "SV5") (pin "8") (pinfunction "8_8") (pintype "passive"))
      (node (ref "SV8") (pin "1") (pinfunction "1_1") (pintype "passive"))
      (node (ref "SV8") (pin "2") (pinfunction "2_2") (pintype "passive"))
      (node (ref "U$1") (pin "P$13") (pinfunction "GND1_P$13") (pintype "bidirectional"))
      (node (ref "U$1") (pin "P$19") (pinfunction "GND2_P$19") (pintype "bidirectional"))
      (node (ref "U$1") (pin "P$21") (pinfunction "GND_P$21") (pintype "bidirectional"))
      (node (ref "U$1") (pin "P$25") (pinfunction "GND3_P$25") (pintype "bidirectional"))
      (node (ref "U$4") (pin "GND") (pinfunction "GND_GND") (pintype "bidirectional"))
      (node (ref "U$4") (pin "GNDO") (pinfunction "GNDO_GNDO") (pintype "bidirectional"))
    )
    (net (code "92") (name "Net-(J5-+)") (class "Default")
      (node (ref "J5") (pin "BATT") (pinfunction "+_BATT") (pintype "passive"))
      (node (ref "U$5") (pin "P$2") (pinfunction "P_P$2") (pintype "passive"))
    )
    (net (code "93") (name "Net-(LED1-PadA)") (class "Default")
      (node (ref "LED1") (pin "A") (pinfunction "A_A") (pintype "passive"))
      (node (ref "R1") (pin "2") (pinfunction "2_2") (pintype "passive"))
    )
    (net (code "94") (name "Net-(LED2-PadA)") (class "Default")
      (node (ref "LED2") (pin "A") (pinfunction "A_A") (pintype "passive"))
      (node (ref "R2") (pin "2") (pinfunction "2_2") (pintype "passive"))
    )
    (net (code "95") (name "Net-(LED3-PadA)") (class "Default")
      (node (ref "LED3") (pin "A") (pinfunction "A_A") (pintype "passive"))
      (node (ref "R3") (pin "2") (pinfunction "2_2") (pintype "passive"))
    )
    (net (code "96") (name "Net-(LED4-PadA)") (class "Default")
      (node (ref "LED4") (pin "A") (pinfunction "A_A") (pintype "passive"))
      (node (ref "R4") (pin "2") (pinfunction "2_2") (pintype "passive"))
    )
    (net (code "97") (name "Net-(LED5-PadA)") (class "Default")
      (node (ref "LED5") (pin "A") (pinfunction "A_A") (pintype "passive"))
      (node (ref "R5") (pin "2") (pinfunction "2_2") (pintype "passive"))
    )
    (net (code "98") (name "Net-(LED6-PadA)") (class "Default")
      (node (ref "LED6") (pin "A") (pinfunction "A_A") (pintype "passive"))
      (node (ref "R6") (pin "2") (pinfunction "2_2") (pintype "passive"))
    )
    (net (code "99") (name "Net-(LED7-PadA)") (class "Default")
      (node (ref "LED7") (pin "A") (pinfunction "A_A") (pintype "passive"))
      (node (ref "R7") (pin "2") (pinfunction "2_2") (pintype "passive"))
    )
    (net (code "100") (name "Net-(U$5-S)") (class "Default")
      (node (ref "U$5") (pin "P$1") (pinfunction "S_P$1") (pintype "passive"))
      (node (ref "U1") (pin "1") (pinfunction "~{A}_1") (pintype "bidirectional"))
      (node (ref "U1") (pin "3") (pinfunction "A_3") (pintype "bidirectional"))
      (node (ref "U2") (pin "1") (pinfunction "~{A}_1") (pintype "bidirectional"))
      (node (ref "U2") (pin "3") (pinfunction "A_3") (pintype "bidirectional"))
      (node (ref "U3") (pin "1") (pinfunction "~{A}_1") (pintype "bidirectional"))
      (node (ref "U3") (pin "3") (pinfunction "A_3") (pintype "bidirectional"))
    )
    (net (code "101") (name "unconnected-(J1-Pad1)") (class "Default")
      (node (ref "J1") (pin "1") (pinfunction "1_1") (pintype "passive"))
    )
    (net (code "102") (name "unconnected-(J1-Pad4)") (class "Default")
      (node (ref "J1") (pin "4") (pinfunction "4_4") (pintype "passive"))
    )
    (net (code "103") (name "unconnected-(J1-Pad5)") (class "Default")
      (node (ref "J1") (pin "5") (pinfunction "5_5") (pintype "passive"))
    )
    (net (code "104") (name "unconnected-(J1-Pad7)") (class "Default")
      (node (ref "J1") (pin "7") (pinfunction "7_7") (pintype "passive"))
    )
    (net (code "105") (name "unconnected-(J1-Pad9)") (class "Default")
      (node (ref "J1") (pin "9") (pinfunction "9_9") (pintype "passive"))
    )
    (net (code "106") (name "unconnected-(J1-Pad10)") (class "Default")
      (node (ref "J1") (pin "10") (pinfunction "10_10") (pintype "passive"))
    )
    (net (code "107") (name "unconnected-(J2-Pad1)") (class "Default")
      (node (ref "J2") (pin "1") (pinfunction "1_1") (pintype "passive"))
    )
    (net (code "108") (name "unconnected-(J2-Pad4)") (class "Default")
      (node (ref "J2") (pin "4") (pinfunction "4_4") (pintype "passive"))
    )
    (net (code "109") (name "unconnected-(J2-Pad5)") (class "Default")
      (node (ref "J2") (pin "5") (pinfunction "5_5") (pintype "passive"))
    )
    (net (code "110") (name "unconnected-(J2-Pad7)") (class "Default")
      (node (ref "J2") (pin "7") (pinfunction "7_7") (pintype "passive"))
    )
    (net (code "111") (name "unconnected-(J2-Pad9)") (class "Default")
      (node (ref "J2") (pin "9") (pinfunction "9_9") (pintype "passive"))
    )
    (net (code "112") (name "unconnected-(J2-Pad10)") (class "Default")
      (node (ref "J2") (pin "10") (pinfunction "10_10") (pintype "passive"))
    )
    (net (code "113") (name "unconnected-(J3-Pad1)") (class "Default")
      (node (ref "J3") (pin "1") (pinfunction "1_1") (pintype "passive"))
    )
    (net (code "114") (name "unconnected-(J3-Pad4)") (class "Default")
      (node (ref "J3") (pin "4") (pinfunction "4_4") (pintype "passive"))
    )
    (net (code "115") (name "unconnected-(J3-Pad5)") (class "Default")
      (node (ref "J3") (pin "5") (pinfunction "5_5") (pintype "passive"))
    )
    (net (code "116") (name "unconnected-(J3-Pad7)") (class "Default")
      (node (ref "J3") (pin "7") (pinfunction "7_7") (pintype "passive"))
    )
    (net (code "117") (name "unconnected-(J3-Pad9)") (class "Default")
      (node (ref "J3") (pin "9") (pinfunction "9_9") (pintype "passive"))
    )
    (net (code "118") (name "unconnected-(J3-Pad10)") (class "Default")
      (node (ref "J3") (pin "10") (pinfunction "10_10") (pintype "passive"))
    )
    (net (code "119") (name "unconnected-(J4-Pad1)") (class "Default")
      (node (ref "J4") (pin "1") (pinfunction "1_1") (pintype "passive"))
    )
    (net (code "120") (name "unconnected-(J4-Pad4)") (class "Default")
      (node (ref "J4") (pin "4") (pinfunction "4_4") (pintype "passive"))
    )
    (net (code "121") (name "unconnected-(J4-Pad5)") (class "Default")
      (node (ref "J4") (pin "5") (pinfunction "5_5") (pintype "passive"))
    )
    (net (code "122") (name "unconnected-(J4-Pad7)") (class "Default")
      (node (ref "J4") (pin "7") (pinfunction "7_7") (pintype "passive"))
    )
    (net (code "123") (name "unconnected-(J4-Pad9)") (class "Default")
      (node (ref "J4") (pin "9") (pinfunction "9_9") (pintype "passive"))
    )
    (net (code "124") (name "unconnected-(J4-Pad10)") (class "Default")
      (node (ref "J4") (pin "10") (pinfunction "10_10") (pintype "passive"))
    )
    (net (code "125") (name "unconnected-(JP1-Pad2)") (class "Default")
      (node (ref "JP1") (pin "2") (pinfunction "2_2") (pintype "passive"))
    )
    (net (code "126") (name "unconnected-(JP1-Pad14)") (class "Default")
      (node (ref "JP1") (pin "14") (pinfunction "14_14") (pintype "passive"))
    )
    (net (code "127") (name "unconnected-(JP1-Pad24)") (class "Default")
      (node (ref "JP1") (pin "24") (pinfunction "24_24") (pintype "passive"))
    )
    (net (code "128") (name "unconnected-(JP1-Pad26)") (class "Default")
      (node (ref "JP1") (pin "26") (pinfunction "26_26") (pintype "passive"))
    )
    (net (code "129") (name "unconnected-(JP1-Pad28)") (class "Default")
      (node (ref "JP1") (pin "28") (pinfunction "28_28") (pintype "passive"))
    )
    (net (code "130") (name "unconnected-(JP1-Pad40)") (class "Default")
      (node (ref "JP1") (pin "40") (pinfunction "40_40") (pintype "passive"))
    )
    (net (code "131") (name "unconnected-(JP2-Pad1)") (class "Default")
      (node (ref "JP2") (pin "1") (pinfunction "1_1") (pintype "passive"))
    )
    (net (code "132") (name "unconnected-(JP2-Pad13)") (class "Default")
      (node (ref "JP2") (pin "13") (pinfunction "13_13") (pintype "passive"))
    )
    (net (code "133") (name "unconnected-(JP2-Pad17)") (class "Default")
      (node (ref "JP2") (pin "17") (pinfunction "17_17") (pintype "passive"))
    )
    (net (code "134") (name "unconnected-(JP2-Pad19)") (class "Default")
      (node (ref "JP2") (pin "19") (pinfunction "19_19") (pintype "passive"))
    )
    (net (code "135") (name "unconnected-(JP2-Pad27)") (class "Default")
      (node (ref "JP2") (pin "27") (pinfunction "27_27") (pintype "passive"))
    )
    (net (code "136") (name "unconnected-(JP2-Pad39)") (class "Default")
      (node (ref "JP2") (pin "39") (pinfunction "39_39") (pintype "passive"))
    )
    (net (code "137") (name "unconnected-(U$1-3V3-PadP$38)") (class "Default")
      (node (ref "U$1") (pin "P$38") (pinfunction "3V3_P$38") (pintype "bidirectional"))
    )
    (net (code "138") (name "unconnected-(U$1-CLK-PadP$1)") (class "Default")
      (node (ref "U$1") (pin "P$1") (pinfunction "CLK_P$1") (pintype "bidirectional"))
    )
    (net (code "139") (name "unconnected-(U$1-P0-PadP$6)") (class "Default")
      (node (ref "U$1") (pin "P$6") (pinfunction "P0_P$6") (pintype "bidirectional"))
    )
    (net (code "140") (name "unconnected-(U$1-P1-PadP$7)") (class "Default")
      (node (ref "U$1") (pin "P$7") (pinfunction "P1_P$7") (pintype "bidirectional"))
    )
    (net (code "141") (name "unconnected-(U$1-P2-PadP$5)") (class "Default")
      (node (ref "U$1") (pin "P$5") (pinfunction "P2_P$5") (pintype "bidirectional"))
    )
    (net (code "142") (name "unconnected-(U$1-P5-PadP$10)") (class "Default")
      (node (ref "U$1") (pin "P$10") (pinfunction "P5_P$10") (pintype "bidirectional"))
    )
    (net (code "143") (name "unconnected-(U$1-P12-PadP$26)") (class "Default")
      (node (ref "U$1") (pin "P$26") (pinfunction "P12_P$26") (pintype "bidirectional"))
    )
    (net (code "144") (name "unconnected-(U$1-P13-PadP$24)") (class "Default")
      (node (ref "U$1") (pin "P$24") (pinfunction "P13_P$24") (pintype "bidirectional"))
    )
    (net (code "145") (name "unconnected-(U$1-P14-PadP$27)") (class "Default")
      (node (ref "U$1") (pin "P$27") (pinfunction "P14_P$27") (pintype "bidirectional"))
    )
    (net (code "146") (name "unconnected-(U$1-P15-PadP$4)") (class "Default")
      (node (ref "U$1") (pin "P$4") (pinfunction "P15_P$4") (pintype "bidirectional"))
    )
    (net (code "147") (name "unconnected-(U$1-P16-PadP$8)") (class "Default")
      (node (ref "U$1") (pin "P$8") (pinfunction "P16_P$8") (pintype "bidirectional"))
    )
    (net (code "148") (name "unconnected-(U$1-P17-PadP$9)") (class "Default")
      (node (ref "U$1") (pin "P$9") (pinfunction "P17_P$9") (pintype "bidirectional"))
    )
    (net (code "149") (name "unconnected-(U$1-P18-PadP$11)") (class "Default")
      (node (ref "U$1") (pin "P$11") (pinfunction "P18_P$11") (pintype "bidirectional"))
    )
    (net (code "150") (name "unconnected-(U$1-P19-PadP$12)") (class "Default")
      (node (ref "U$1") (pin "P$12") (pinfunction "P19_P$12") (pintype "bidirectional"))
    )
    (net (code "151") (name "unconnected-(U$1-P21-PadP$14)") (class "Default")
      (node (ref "U$1") (pin "P$14") (pinfunction "P21_P$14") (pintype "bidirectional"))
    )
    (net (code "152") (name "unconnected-(U$1-P22-PadP$17)") (class "Default")
      (node (ref "U$1") (pin "P$17") (pinfunction "P22_P$17") (pintype "bidirectional"))
    )
    (net (code "153") (name "unconnected-(U$1-P23-PadP$18)") (class "Default")
      (node (ref "U$1") (pin "P$18") (pinfunction "P23_P$18") (pintype "bidirectional"))
    )
    (net (code "154") (name "unconnected-(U$1-P25-PadP$30)") (class "Default")
      (node (ref "U$1") (pin "P$30") (pinfunction "P25_P$30") (pintype "bidirectional"))
    )
    (net (code "155") (name "unconnected-(U$1-P26-PadP$29)") (class "Default")
      (node (ref "U$1") (pin "P$29") (pinfunction "P26_P$29") (pintype "bidirectional"))
    )
    (net (code "156") (name "unconnected-(U$1-P27-PadP$28)") (class "Default")
      (node (ref "U$1") (pin "P$28") (pinfunction "P27_P$28") (pintype "bidirectional"))
    )
    (net (code "157") (name "unconnected-(U$1-P32-PadP$32)") (class "Default")
      (node (ref "U$1") (pin "P$32") (pinfunction "P32_P$32") (pintype "bidirectional"))
    )
    (net (code "158") (name "unconnected-(U$1-P33-PadP$31)") (class "Default")
      (node (ref "U$1") (pin "P$31") (pinfunction "P33_P$31") (pintype "bidirectional"))
    )
    (net (code "159") (name "unconnected-(U$1-SD0-PadP$2)") (class "Default")
      (node (ref "U$1") (pin "P$2") (pinfunction "SD0_P$2") (pintype "bidirectional"))
    )
    (net (code "160") (name "unconnected-(U$1-SD1-PadP$3)") (class "Default")
      (node (ref "U$1") (pin "P$3") (pinfunction "SD1_P$3") (pintype "bidirectional"))
    )
    (net (code "161") (name "unconnected-(U$1-SD2-PadP$23)") (class "Default")
      (node (ref "U$1") (pin "P$23") (pinfunction "SD2_P$23") (pintype "bidirectional"))
    )
    (net (code "162") (name "unconnected-(U$1-SD3-PadP$22)") (class "Default")
      (node (ref "U$1") (pin "P$22") (pinfunction "SD3_P$22") (pintype "bidirectional"))
    )
    (net (code "163") (name "unconnected-(U$1-SVN-PadP$35)") (class "Default")
      (node (ref "U$1") (pin "P$35") (pinfunction "SVN_P$35") (pintype "bidirectional"))
    )
    (net (code "164") (name "unconnected-(U$1-SVP-PadP$36)") (class "Default")
      (node (ref "U$1") (pin "P$36") (pinfunction "SVP_P$36") (pintype "bidirectional"))
    )
  )
)
